# esquematico_microcontrolador.net
KiCad netlist of a schematic drawn in Altium Designer
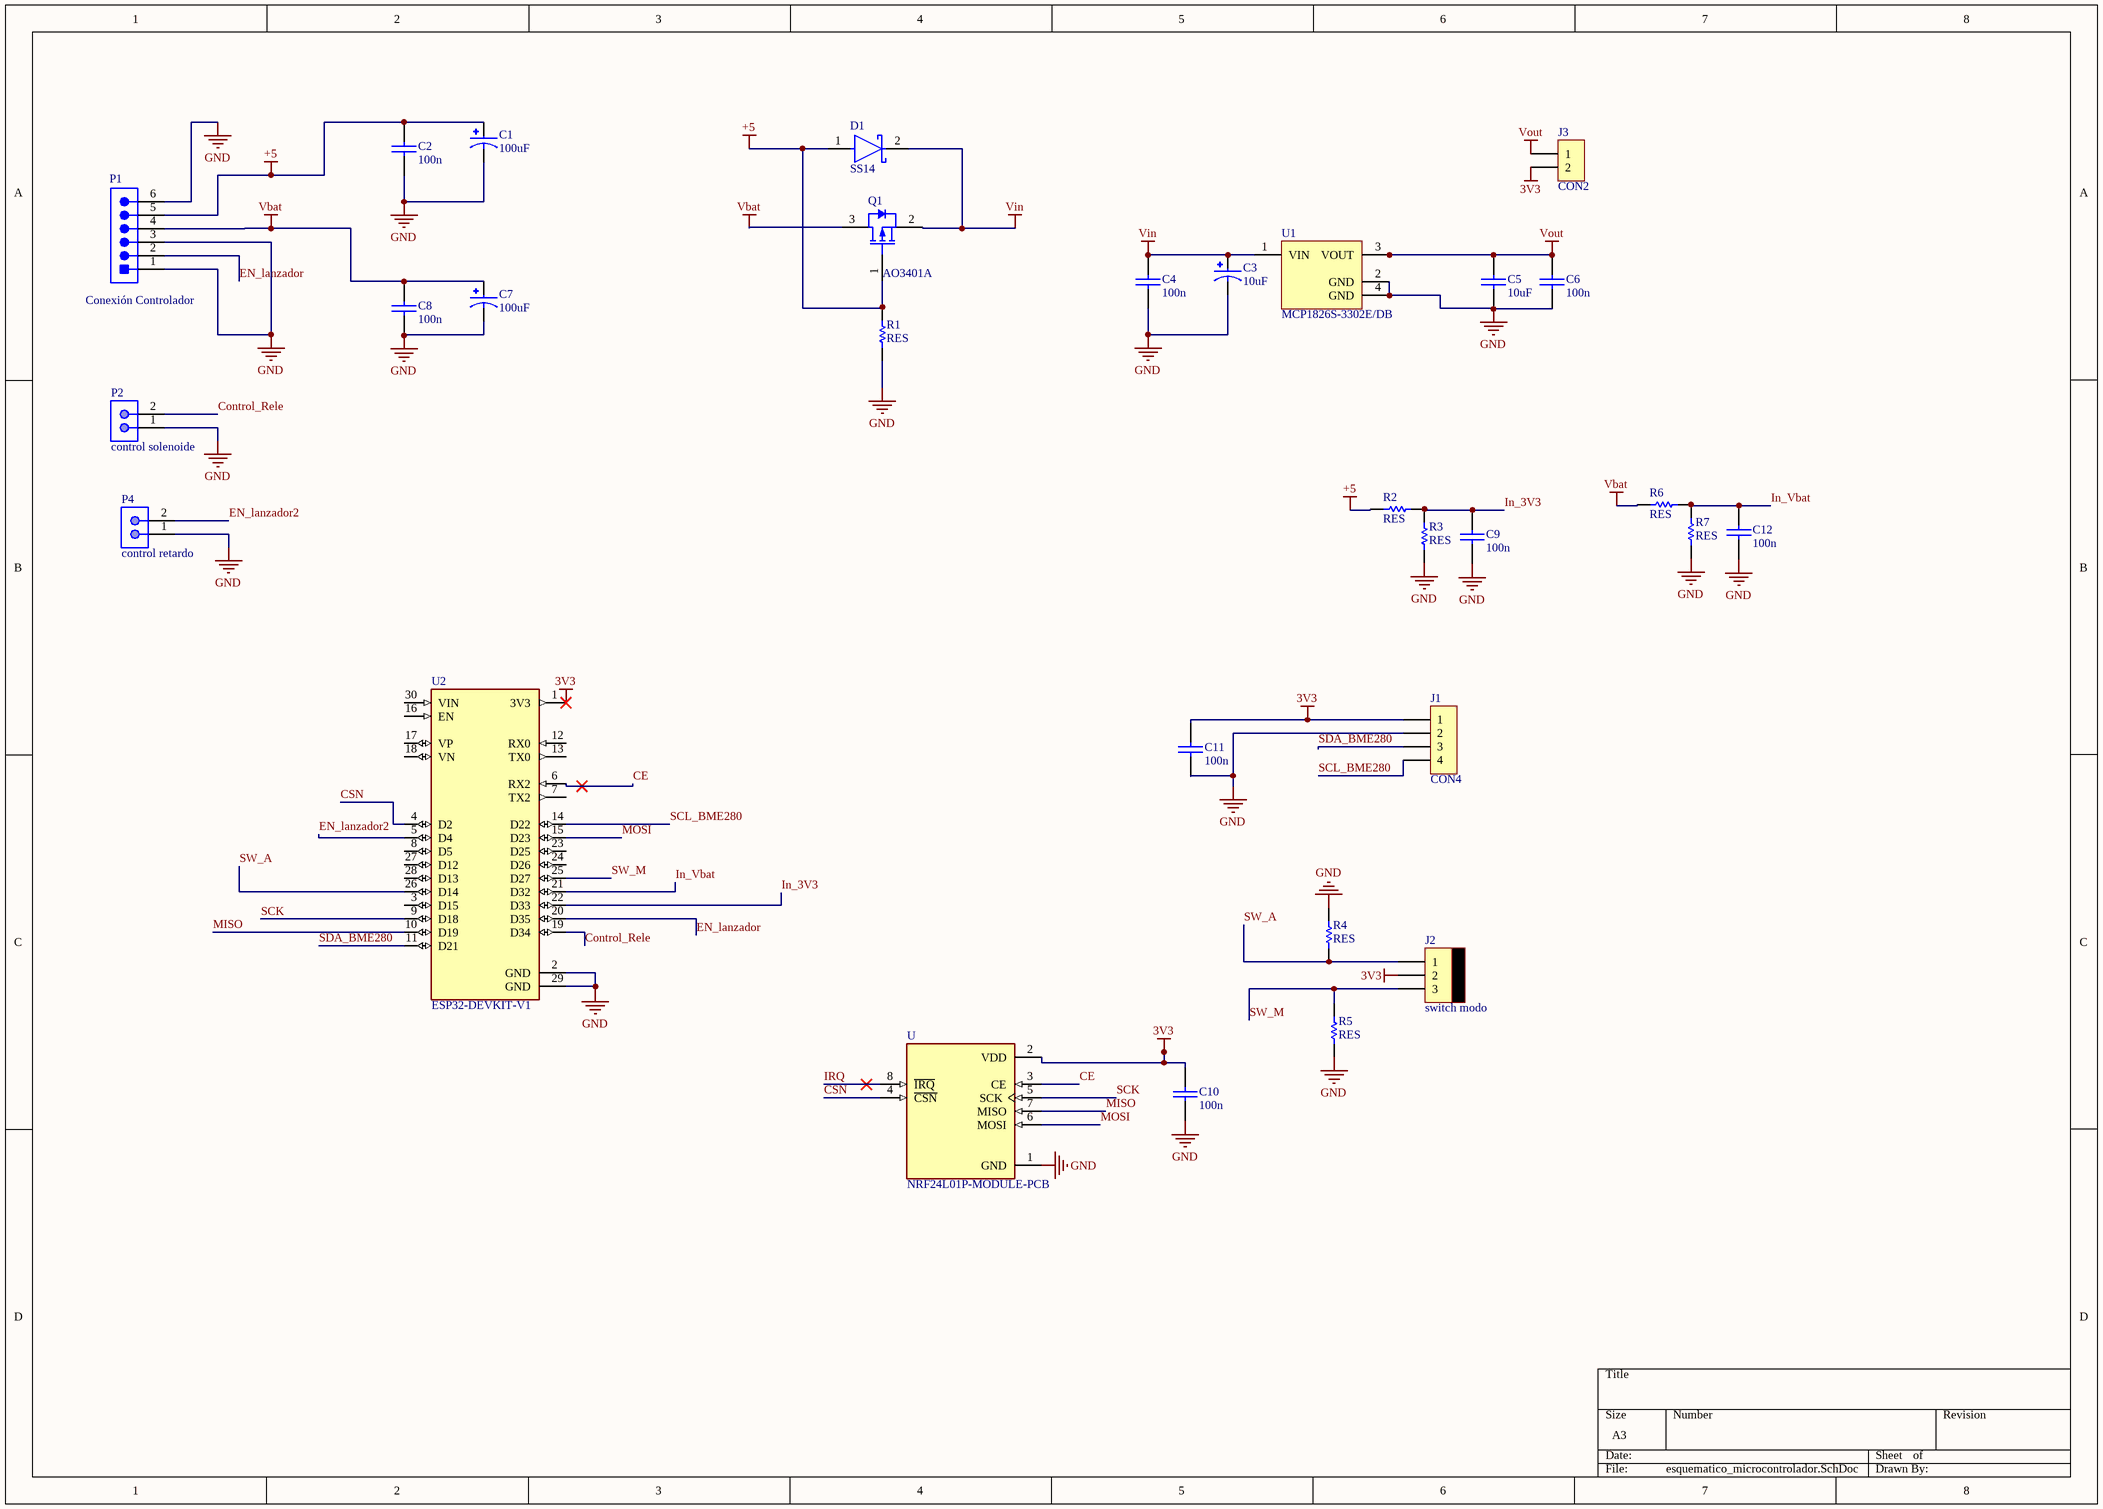
[diagram p0: esquematico_microcontrolador.SchDoc]

(export (version "E")
  (design (tool "Eeschema 10.0.6"))
  (components
    (comp (ref "C1")
      (value "100uF")
      (footprint "CAP_EEEFN1V100R")
      (description "10µF 35V Aluminum Electrolytic Capacitors Radial, Can - SMD 1.35Ohm @ 100kHz 2000 Hrs @ 105°C")
      (fields (field (name "MF") "Panasonic") (field (name "MP") "EEEFN1V100R"))
      (libsource (lib "EEEFN1V100R") (part "EEEFN1V100R"))
    )
    (comp (ref "C2") (value "100n") (footprint "1206") (libsource (lib "LIBEBAL") (part "CAP")))
    (comp (ref "C3")
      (value "10uF")
      (footprint "CAP_EEEFN1V100R")
      (description "10µF 35V Aluminum Electrolytic Capacitors Radial, Can - SMD 1.35Ohm @ 100kHz 2000 Hrs @ 105°C")
      (fields (field (name "MF") "Panasonic") (field (name "MP") "EEEFN1V100R"))
      (libsource (lib "EEEFN1V100R") (part "EEEFN1V100R"))
    )
    (comp (ref "C4") (value "100n") (footprint "1206") (libsource (lib "LIBEBAL") (part "CAP")))
    (comp (ref "C5")
      (value "10uF")
      (footprint "1206")
      (description "Capacitor 10uF a 22uF X5R 1206")
      (libsource (lib "LIB PIO IX") (part "CAP"))
    )
    (comp (ref "C6")
      (value "100n")
      (footprint "1206")
      (description "Capacitor 100n NP0 1206 o 0805 (cambiar footprint 0805)")
      (libsource (lib "LIB PIO IX") (part "CAP"))
    )
    (comp (ref "C7")
      (value "100uF")
      (footprint "CAP_EEEFN1V100R")
      (description "10µF 35V Aluminum Electrolytic Capacitors Radial, Can - SMD 1.35Ohm @ 100kHz 2000 Hrs @ 105°C")
      (fields (field (name "MF") "Panasonic") (field (name "MP") "EEEFN1V100R"))
      (libsource (lib "EEEFN1V100R") (part "EEEFN1V100R"))
    )
    (comp (ref "C8") (value "100n") (footprint "1206") (libsource (lib "LIBEBAL") (part "CAP")))
    (comp (ref "C9") (value "100n") (footprint "0805") (libsource (lib "LIBEBAL") (part "CAP")))
    (comp (ref "C10") (value "100n") (footprint "0805") (libsource (lib "LIBEBAL") (part "CAP")))
    (comp (ref "C11")
      (value "100n")
      (footprint "0805")
      (description "Capacitor 100n NP0 1206 o 0805 (cambiar footprint 0805)")
      (libsource (lib "LIB PIO IX") (part "CAP"))
    )
    (comp (ref "C12") (value "100n") (footprint "0805") (libsource (lib "LIBEBAL") (part "CAP")))
    (comp (ref "D1")
      (value "SS14")
      (footprint "FP-403AE-MFG")
      (description "DIODE SCHOTTKY 40V 1A SMA")
      (fields
        (field (name "MANUFACTURER") "ON Semiconductor")
        (field (name "OCTOPART") "https://octopart.com/ss14-on+semiconductor-29205033")
      )
      (libsource (lib "Altium Content Vault") (part "360ad2f4ac25a952324d13796385471"))
    )
    (comp (ref "J1") (value "CON4") (footprint "SIP4") (libsource (lib "LIBEBAL") (part "CON4")))
    (comp (ref "J2") (value "switch modo") (footprint "MOLEX3") (libsource (lib "LIBEBAL") (part "MOLEX3")))
    (comp (ref "J3") (value "CON2") (footprint "SIP2") (libsource (lib "LIB PIO IX") (part "CON2")))
    (comp (ref "P1")
      (value "Conexión Controlador")
      (footprint "MOLX-22-23-2061_V")
      (fields (field (name "MANUFACTURER") "Molex"))
      (libsource (lib "Altium Content Vault") (part "CN-1P-M-R6"))
    )
    (comp (ref "P2")
      (value "control solenoide")
      (footprint "MOLX-22-23-2021_V")
      (fields (field (name "PARTNUMBER") "22-23-2021"))
      (libsource (lib "Altium Content Vault") (part "CN-1P-M-R2"))
    )
    (comp (ref "P4")
      (value "control retardo")
      (footprint "MOLX-22-23-2021_V")
      (fields (field (name "PARTNUMBER") "22-23-2021"))
      (libsource (lib "Altium Content Vault") (part "CN-1P-M-R2"))
    )
    (comp (ref "Q1")
      (value "AO3401A")
      (footprint "AO-SOT-23-3L_V")
      (description "P-Channel MOSFET, 30 V, 4 A, -55 to 150 degC, 3-Pin SOT-23-3L, RoHS, Tape and Reel")
      (fields (field (name "MANUFACTURER") "Alpha and Omega"))
      (libsource (lib "Altium Content Vault") (part "PEMOS-GSD-3"))
    )
    (comp (ref "R1") (value "RES") (footprint "0805") (libsource (lib "LIB PIO IX") (part "RES")))
    (comp (ref "R2") (value "RES") (footprint "0805") (libsource (lib "LIB PIO IX") (part "RES")))
    (comp (ref "R3") (value "RES") (footprint "0805") (libsource (lib "LIB PIO IX") (part "RES")))
    (comp (ref "R4") (value "RES") (footprint "0805") (libsource (lib "LIB PIO IX") (part "RES")))
    (comp (ref "R5") (value "RES") (footprint "0805") (libsource (lib "LIB PIO IX") (part "RES")))
    (comp (ref "R6") (value "RES") (footprint "0805") (libsource (lib "LIB PIO IX") (part "RES")))
    (comp (ref "R7") (value "RES") (footprint "0805") (libsource (lib "LIB PIO IX") (part "RES")))
    (comp (ref "U")
      (value "NRF24L01P-MODULE-PCB")
      (footprint "XCVR_NRF24L01P-MODULE-PCB")
      (description "- Transceiver For Use With nRF24L01+")
      (fields (field (name "MF") "Nordic Semiconductor"))
      (libsource (lib "NRF24L01P-MODULE-PCB") (part "NRF24L01P-MODULE-PCB"))
    )
    (comp (ref "U1")
      (value "MCP1826S-3302E/DB")
      (footprint "SOT-223-DB3_L")
      (description "1000 mA, Low Voltage, Low Quiescent Current LDO Regulator, 3-Pin SOT-223, Extended Temperature")
      (libsource (lib "Altium Content Vault") (part "PM-LINEREG-MCP1826-IL4"))
    )
    (comp (ref "U2")
      (value "ESP32-DEVKIT-V1")
      (footprint "MODULE_ESP32_DEVKIT_V1")
      (fields (field (name "MF") "Do it"))
      (libsource (lib "ESP32-DEVKIT-V1") (part "ESP32-DEVKIT-V1"))
    )
  )
  (nets
    (net (code "1") (name "+5") (class "Default")
      (node (ref "C1") (pin "1") (pinfunction "1_1") (pintype "passive"))
      (node (ref "C2") (pin "1") (pinfunction "1_1") (pintype "passive"))
      (node (ref "D1") (pin "1") (pinfunction "A_1") (pintype "passive"))
      (node (ref "P1") (pin "5") (pinfunction "5_5") (pintype "passive"))
      (node (ref "Q1") (pin "1") (pinfunction "GATE_1") (pintype "passive"))
      (node (ref "R1") (pin "2") (pinfunction "2_2") (pintype "passive"))
      (node (ref "R2") (pin "2") (pinfunction "2_2") (pintype "passive"))
    )
    (net (code "2") (name "/CE") (class "Default")
      (node (ref "U") (pin "3") (pinfunction "CE_3") (pintype "input"))
      (node (ref "U2") (pin "6") (pinfunction "RX2_6") (pintype "input"))
    )
    (net (code "3") (name "/CSN") (class "Default")
      (node (ref "U") (pin "4") (pinfunction "~{CSN}_4") (pintype "input"))
      (node (ref "U2") (pin "4") (pinfunction "D2_4") (pintype "bidirectional"))
    )
    (net (code "4") (name "/Control_Rele") (class "Default")
      (node (ref "P2") (pin "2") (pinfunction "2_2") (pintype "passive"))
      (node (ref "U2") (pin "19") (pinfunction "D34_19") (pintype "bidirectional"))
    )
    (net (code "5") (name "/EN_lanzador") (class "Default")
      (node (ref "P1") (pin "2") (pinfunction "2_2") (pintype "passive"))
      (node (ref "U2") (pin "20") (pinfunction "D35_20") (pintype "bidirectional"))
    )
    (net (code "6") (name "/EN_lanzador2") (class "Default")
      (node (ref "P4") (pin "2") (pinfunction "2_2") (pintype "passive"))
      (node (ref "U2") (pin "5") (pinfunction "D4_5") (pintype "bidirectional"))
    )
    (net (code "7") (name "/IRQ") (class "Default")
      (node (ref "U") (pin "8") (pinfunction "~{IRQ}_8") (pintype "input"))
    )
    (net (code "8") (name "/In_3V3") (class "Default")
      (node (ref "C9") (pin "1") (pinfunction "1_1") (pintype "passive"))
      (node (ref "R2") (pin "1") (pinfunction "1_1") (pintype "passive"))
      (node (ref "R3") (pin "2") (pinfunction "2_2") (pintype "passive"))
      (node (ref "U2") (pin "22") (pinfunction "D33_22") (pintype "bidirectional"))
    )
    (net (code "9") (name "/In_Vbat") (class "Default")
      (node (ref "C12") (pin "1") (pinfunction "1_1") (pintype "passive"))
      (node (ref "R6") (pin "1") (pinfunction "1_1") (pintype "passive"))
      (node (ref "R7") (pin "2") (pinfunction "2_2") (pintype "passive"))
      (node (ref "U2") (pin "21") (pinfunction "D32_21") (pintype "bidirectional"))
    )
    (net (code "10") (name "/MISO") (class "Default")
      (node (ref "U") (pin "7") (pinfunction "MISO_7") (pintype "input"))
      (node (ref "U2") (pin "10") (pinfunction "D19_10") (pintype "bidirectional"))
    )
    (net (code "11") (name "/MOSI") (class "Default")
      (node (ref "U") (pin "6") (pinfunction "MOSI_6") (pintype "input"))
      (node (ref "U2") (pin "15") (pinfunction "D23_15") (pintype "bidirectional"))
    )
    (net (code "12") (name "/SCK") (class "Default")
      (node (ref "U") (pin "5") (pinfunction "SCK_5") (pintype "input"))
      (node (ref "U2") (pin "9") (pinfunction "D18_9") (pintype "bidirectional"))
    )
    (net (code "13") (name "/SCL_BME280") (class "Default")
      (node (ref "J1") (pin "4") (pinfunction "4_4") (pintype "passive"))
      (node (ref "U2") (pin "14") (pinfunction "D22_14") (pintype "bidirectional"))
    )
    (net (code "14") (name "/SDA_BME280") (class "Default")
      (node (ref "J1") (pin "3") (pinfunction "3_3") (pintype "passive"))
      (node (ref "U2") (pin "11") (pinfunction "D21_11") (pintype "bidirectional"))
    )
    (net (code "15") (name "/SW_A") (class "Default")
      (node (ref "J2") (pin "1") (pinfunction "1_1") (pintype "passive"))
      (node (ref "R4") (pin "1") (pinfunction "1_1") (pintype "passive"))
      (node (ref "U2") (pin "26") (pinfunction "D14_26") (pintype "bidirectional"))
    )
    (net (code "16") (name "/SW_M") (class "Default")
      (node (ref "J2") (pin "3") (pinfunction "3_3") (pintype "passive"))
      (node (ref "R5") (pin "2") (pinfunction "2_2") (pintype "passive"))
      (node (ref "U2") (pin "25") (pinfunction "D27_25") (pintype "bidirectional"))
    )
    (net (code "17") (name "3V3") (class "Default")
      (node (ref "C10") (pin "1") (pinfunction "1_1") (pintype "passive"))
      (node (ref "C11") (pin "1") (pinfunction "1_1") (pintype "passive"))
      (node (ref "J1") (pin "1") (pinfunction "1_1") (pintype "passive"))
      (node (ref "J2") (pin "2") (pinfunction "2_2") (pintype "passive"))
      (node (ref "J3") (pin "2") (pinfunction "2_2") (pintype "passive"))
      (node (ref "U") (pin "2") (pinfunction "VDD_2") (pintype "power_in"))
      (node (ref "U2") (pin "1") (pinfunction "3V3_1") (pintype "output"))
    )
    (net (code "18") (name "GND") (class "Default")
      (node (ref "C1") (pin "2") (pinfunction "2_2") (pintype "passive"))
      (node (ref "C10") (pin "2") (pinfunction "2_2") (pintype "passive"))
      (node (ref "C11") (pin "2") (pinfunction "2_2") (pintype "passive"))
      (node (ref "C12") (pin "2") (pinfunction "2_2") (pintype "passive"))
      (node (ref "C2") (pin "2") (pinfunction "2_2") (pintype "passive"))
      (node (ref "C3") (pin "2") (pinfunction "2_2") (pintype "passive"))
      (node (ref "C4") (pin "2") (pinfunction "2_2") (pintype "passive"))
      (node (ref "C5") (pin "2") (pinfunction "2_2") (pintype "passive"))
      (node (ref "C6") (pin "2") (pinfunction "2_2") (pintype "passive"))
      (node (ref "C7") (pin "2") (pinfunction "2_2") (pintype "passive"))
      (node (ref "C8") (pin "2") (pinfunction "2_2") (pintype "passive"))
      (node (ref "C9") (pin "2") (pinfunction "2_2") (pintype "passive"))
      (node (ref "J1") (pin "2") (pinfunction "2_2") (pintype "passive"))
      (node (ref "P1") (pin "1") (pinfunction "1_1") (pintype "passive"))
      (node (ref "P1") (pin "3") (pinfunction "3_3") (pintype "passive"))
      (node (ref "P1") (pin "6") (pinfunction "6_6") (pintype "passive"))
      (node (ref "P2") (pin "1") (pinfunction "1_1") (pintype "passive"))
      (node (ref "P4") (pin "1") (pinfunction "1_1") (pintype "passive"))
      (node (ref "R1") (pin "1") (pinfunction "1_1") (pintype "passive"))
      (node (ref "R3") (pin "1") (pinfunction "1_1") (pintype "passive"))
      (node (ref "R4") (pin "2") (pinfunction "2_2") (pintype "passive"))
      (node (ref "R5") (pin "1") (pinfunction "1_1") (pintype "passive"))
      (node (ref "R7") (pin "1") (pinfunction "1_1") (pintype "passive"))
      (node (ref "U") (pin "1") (pinfunction "GND_1") (pintype "power_in"))
      (node (ref "U1") (pin "2") (pinfunction "GND_2") (pintype "power_in"))
      (node (ref "U1") (pin "4") (pinfunction "GND_4") (pintype "power_in"))
      (node (ref "U2") (pin "2") (pinfunction "GND_2") (pintype "power_in"))
      (node (ref "U2") (pin "29") (pinfunction "GND_29") (pintype "power_in"))
    )
    (net (code "19") (name "Vbat") (class "Default")
      (node (ref "C7") (pin "1") (pinfunction "1_1") (pintype "passive"))
      (node (ref "C8") (pin "1") (pinfunction "1_1") (pintype "passive"))
      (node (ref "P1") (pin "4") (pinfunction "4_4") (pintype "passive"))
      (node (ref "Q1") (pin "3") (pinfunction "DRAIN_3") (pintype "passive"))
      (node (ref "R6") (pin "2") (pinfunction "2_2") (pintype "passive"))
    )
    (net (code "20") (name "Vin") (class "Default")
      (node (ref "C3") (pin "1") (pinfunction "1_1") (pintype "passive"))
      (node (ref "C4") (pin "1") (pinfunction "1_1") (pintype "passive"))
      (node (ref "D1") (pin "2") (pinfunction "C_2") (pintype "passive"))
      (node (ref "Q1") (pin "2") (pinfunction "SOURCE_2") (pintype "passive"))
      (node (ref "U1") (pin "1") (pinfunction "VIN_1") (pintype "power_in"))
    )
    (net (code "21") (name "Vout") (class "Default")
      (node (ref "C5") (pin "1") (pinfunction "1_1") (pintype "passive"))
      (node (ref "C6") (pin "1") (pinfunction "1_1") (pintype "passive"))
      (node (ref "J3") (pin "1") (pinfunction "1_1") (pintype "passive"))
      (node (ref "U1") (pin "3") (pinfunction "VOUT_3") (pintype "power_in"))
    )
    (net (code "22") (name "unconnected-(U2-D5-Pad8)") (class "Default")
      (node (ref "U2") (pin "8") (pinfunction "D5_8") (pintype "bidirectional"))
    )
    (net (code "23") (name "unconnected-(U2-D12-Pad27)") (class "Default")
      (node (ref "U2") (pin "27") (pinfunction "D12_27") (pintype "bidirectional"))
    )
    (net (code "24") (name "unconnected-(U2-D13-Pad28)") (class "Default")
      (node (ref "U2") (pin "28") (pinfunction "D13_28") (pintype "bidirectional"))
    )
    (net (code "25") (name "unconnected-(U2-D15-Pad3)") (class "Default")
      (node (ref "U2") (pin "3") (pinfunction "D15_3") (pintype "bidirectional"))
    )
    (net (code "26") (name "unconnected-(U2-D25-Pad23)") (class "Default")
      (node (ref "U2") (pin "23") (pinfunction "D25_23") (pintype "bidirectional"))
    )
    (net (code "27") (name "unconnected-(U2-D26-Pad24)") (class "Default")
      (node (ref "U2") (pin "24") (pinfunction "D26_24") (pintype "bidirectional"))
    )
    (net (code "28") (name "unconnected-(U2-EN-Pad16)") (class "Default")
      (node (ref "U2") (pin "16") (pinfunction "EN_16") (pintype "input"))
    )
    (net (code "29") (name "unconnected-(U2-RX0-Pad12)") (class "Default")
      (node (ref "U2") (pin "12") (pinfunction "RX0_12") (pintype "input"))
    )
    (net (code "30") (name "unconnected-(U2-TX0-Pad13)") (class "Default")
      (node (ref "U2") (pin "13") (pinfunction "TX0_13") (pintype "output"))
    )
    (net (code "31") (name "unconnected-(U2-TX2-Pad7)") (class "Default")
      (node (ref "U2") (pin "7") (pinfunction "TX2_7") (pintype "output"))
    )
    (net (code "32") (name "unconnected-(U2-VIN-Pad30)") (class "Default")
      (node (ref "U2") (pin "30") (pinfunction "VIN_30") (pintype "input"))
    )
    (net (code "33") (name "unconnected-(U2-VN-Pad18)") (class "Default")
      (node (ref "U2") (pin "18") (pinfunction "VN_18") (pintype "bidirectional"))
    )
    (net (code "34") (name "unconnected-(U2-VP-Pad17)") (class "Default")
      (node (ref "U2") (pin "17") (pinfunction "VP_17") (pintype "bidirectional"))
    )
  )
)
